# 02ux.net
KiCad netlist of a schematic drawn in Altium Designer
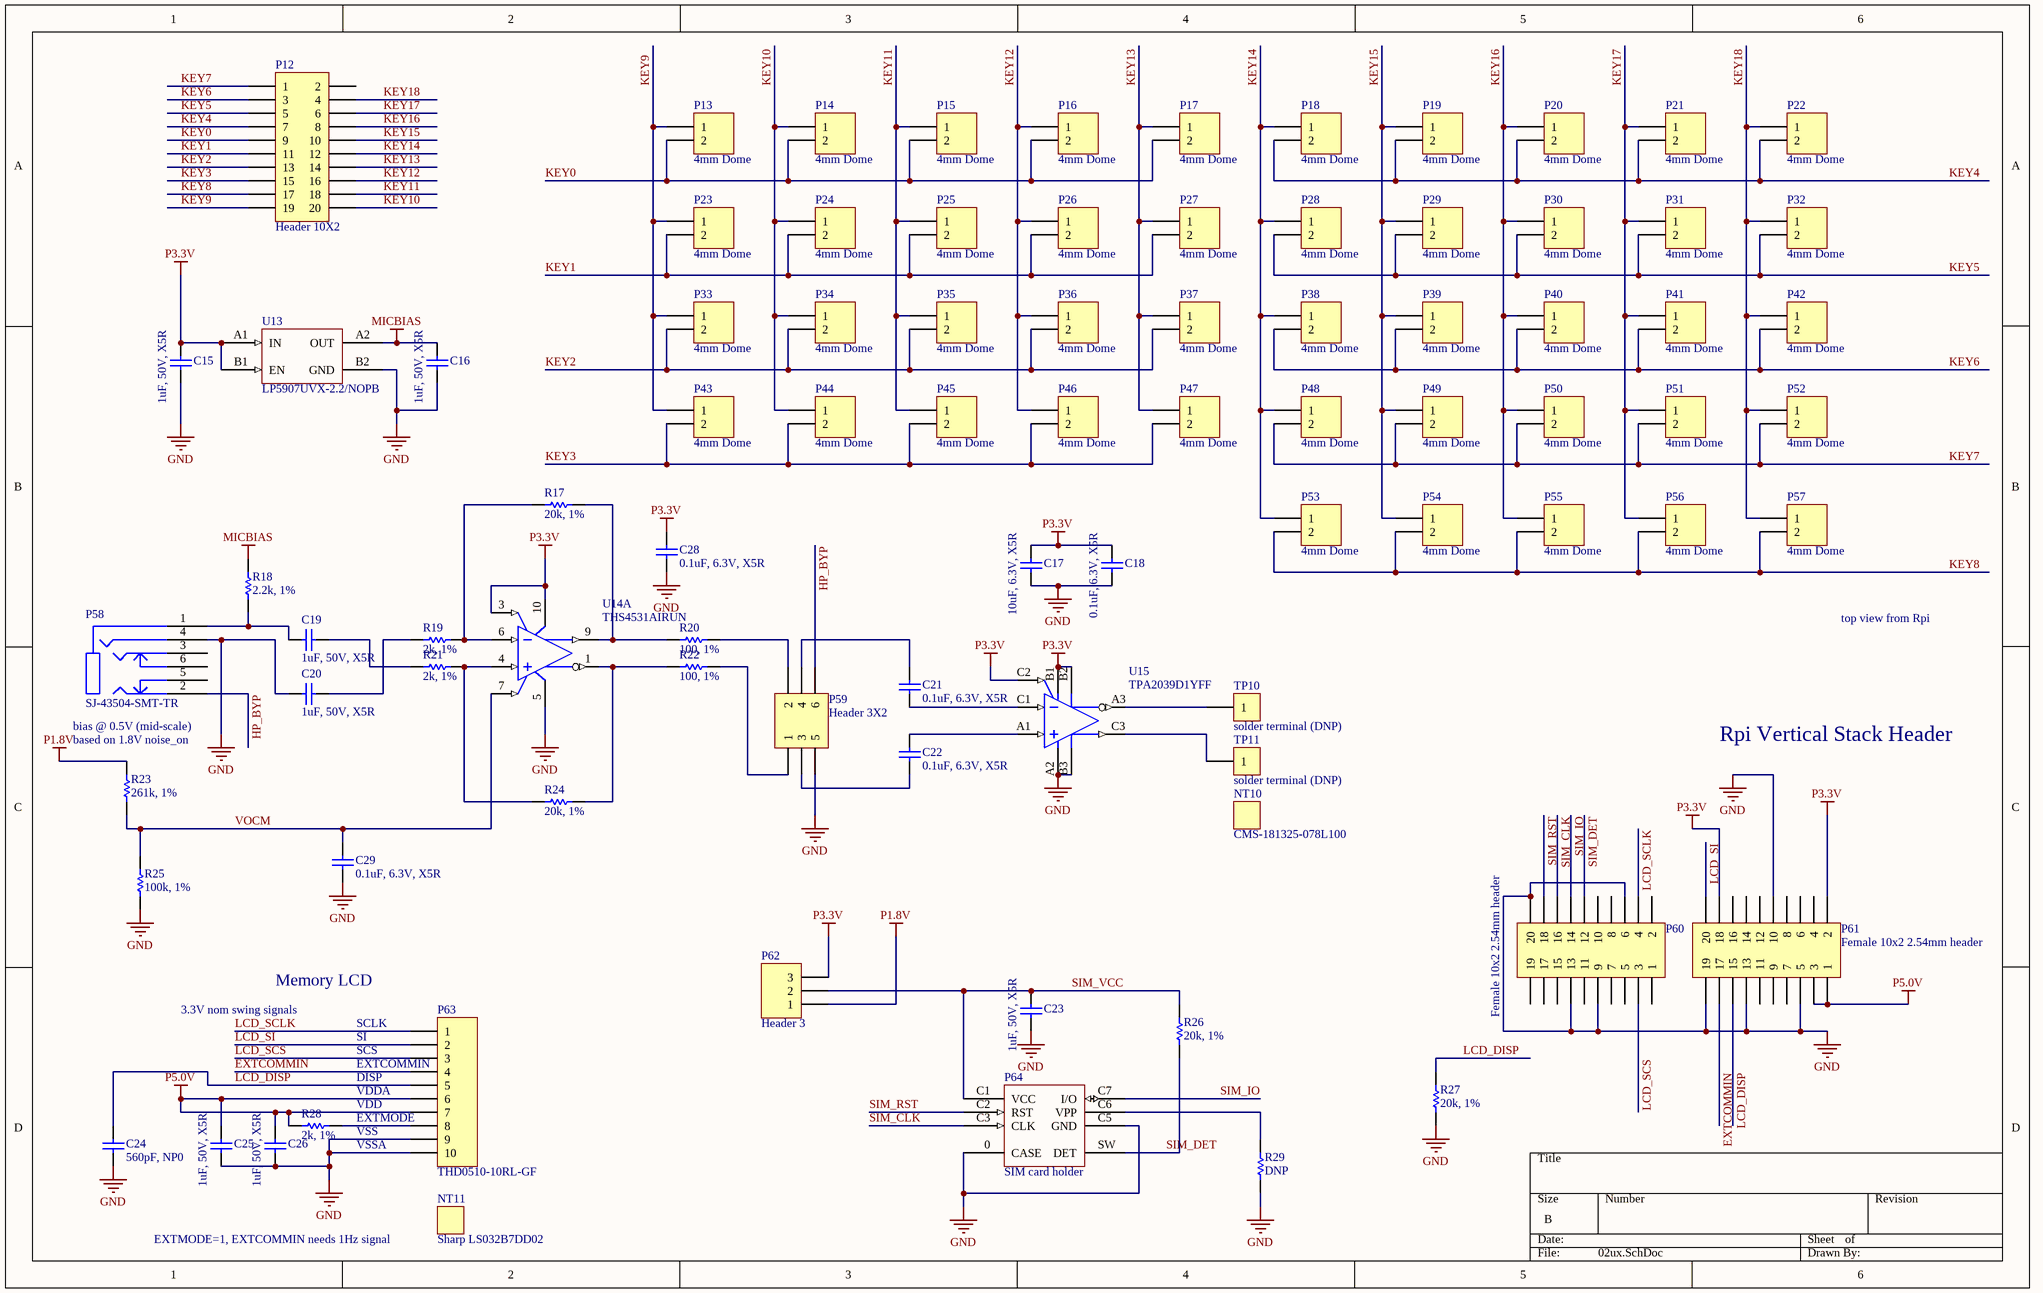
[diagram p0: 02ux.SchDoc]

(export (version "E")
  (design (tool "Eeschema 10.0.6"))
  (components
    (comp (ref "C15")
      (value "1uF, 50V, X5R")
      (footprint "B_CAP0603")
      (description "Capacitor (Semiconductor SIM Model)")
      (fields (field (name "MPN") "CL10A105KB8NNNC"))
      (libsource (lib "Miscellaneous Devices") (part "Cap Semi"))
    )
    (comp (ref "C16")
      (value "1uF, 50V, X5R")
      (footprint "B_CAP0603")
      (description "Capacitor (Semiconductor SIM Model)")
      (fields (field (name "MPN") "CL10A105KB8NNNC"))
      (libsource (lib "Miscellaneous Devices") (part "Cap Semi"))
    )
    (comp (ref "C17")
      (value "10uF, 6.3V, X5R")
      (footprint "B_CAP0603")
      (description "Capacitor (Semiconductor SIM Model)")
      (fields (field (name "MPN") "CL10A106MQ8NNNC"))
      (libsource (lib "Miscellaneous Devices") (part "Cap Semi"))
    )
    (comp (ref "C18")
      (value "0.1uF, 6.3V, X5R")
      (footprint "B_CAP0603")
      (description "Capacitor (Semiconductor SIM Model)")
      (fields (field (name "MPN") "ANY"))
      (libsource (lib "Miscellaneous Devices") (part "Cap Semi"))
    )
    (comp (ref "C19")
      (value "1uF, 50V, X5R")
      (footprint "B_CAP0603")
      (description "Capacitor (Semiconductor SIM Model)")
      (fields (field (name "MPN") "CL10A105KB8NNNC"))
      (libsource (lib "Miscellaneous Devices") (part "Cap Semi"))
    )
    (comp (ref "C20")
      (value "1uF, 50V, X5R")
      (footprint "B_CAP0603")
      (description "Capacitor (Semiconductor SIM Model)")
      (fields (field (name "MPN") "CL10A105KB8NNNC"))
      (libsource (lib "Miscellaneous Devices") (part "Cap Semi"))
    )
    (comp (ref "C21")
      (value "0.1uF, 6.3V, X5R")
      (footprint "B_CAP0603")
      (description "Capacitor (Semiconductor SIM Model)")
      (fields (field (name "MPN") "ANY"))
      (libsource (lib "Miscellaneous Devices") (part "Cap Semi"))
    )
    (comp (ref "C22")
      (value "0.1uF, 6.3V, X5R")
      (footprint "B_CAP0603")
      (description "Capacitor (Semiconductor SIM Model)")
      (fields (field (name "MPN") "ANY"))
      (libsource (lib "Miscellaneous Devices") (part "Cap Semi"))
    )
    (comp (ref "C23")
      (value "1uF, 50V, X5R")
      (footprint "B_CAP0603")
      (description "Capacitor (Semiconductor SIM Model)")
      (fields (field (name "MPN") "CL10A105KB8NNNC"))
      (libsource (lib "Miscellaneous Devices") (part "Cap Semi"))
    )
    (comp (ref "C24")
      (value "560pF, NP0")
      (footprint "B_CAP0402")
      (description "Capacitor (Semiconductor SIM Model)")
      (fields (field (name "MPN") "GRM0335C1E561JA01D"))
      (libsource (lib "Miscellaneous Devices") (part "Cap Semi"))
    )
    (comp (ref "C25")
      (value "1uF, 50V, X5R")
      (footprint "B_CAP0603")
      (description "Capacitor (Semiconductor SIM Model)")
      (fields (field (name "MPN") "CL10A105KB8NNNC"))
      (libsource (lib "Miscellaneous Devices") (part "Cap Semi"))
    )
    (comp (ref "C26")
      (value "1uF, 50V, X5R")
      (footprint "B_CAP0603")
      (description "Capacitor (Semiconductor SIM Model)")
      (fields (field (name "MPN") "CL10A105KB8NNNC"))
      (libsource (lib "Miscellaneous Devices") (part "Cap Semi"))
    )
    (comp (ref "C28")
      (value "0.1uF, 6.3V, X5R")
      (footprint "B_CAP0603")
      (description "Capacitor (Semiconductor SIM Model)")
      (fields (field (name "MPN") "ANY"))
      (libsource (lib "Miscellaneous Devices") (part "Cap Semi"))
    )
    (comp (ref "C29")
      (value "0.1uF, 6.3V, X5R")
      (footprint "B_CAP0603")
      (description "Capacitor (Semiconductor SIM Model)")
      (fields (field (name "MPN") "ANY"))
      (libsource (lib "Miscellaneous Devices") (part "Cap Semi"))
    )
    (comp (ref "NT10")
      (value "CMS-181325-078L100")
      (description "Placeholder for non-board BOM items")
      (libsource (lib "commonsch") (part "NOTE"))
    )
    (comp (ref "NT11")
      (value "Sharp LS032B7DD02")
      (description "Placeholder for non-board BOM items")
      (fields (field (name "MPN") "LS032B7DD02"))
      (libsource (lib "commonsch") (part "NOTE"))
    )
    (comp (ref "P12")
      (value "Header 10X2")
      (footprint "HDR2X10")
      (description "Header, 10-Pin, Dual row")
      (fields (field (name "PUBLISHER") "Altium Limited"))
      (libsource (lib "Miscellaneous Connectors") (part "Header 10X2"))
    )
    (comp (ref "P13")
      (value "4mm Dome")
      (footprint "4MM_DOME_SW")
      (description "Header, 2-Pin")
      (fields (field (name "PUBLISHER") "Altium Limited"))
      (libsource (lib "Miscellaneous Connectors") (part "Header 2"))
    )
    (comp (ref "P14")
      (value "4mm Dome")
      (footprint "4MM_DOME_SW")
      (description "Header, 2-Pin")
      (fields (field (name "PUBLISHER") "Altium Limited"))
      (libsource (lib "Miscellaneous Connectors") (part "Header 2"))
    )
    (comp (ref "P15")
      (value "4mm Dome")
      (footprint "4MM_DOME_SW")
      (description "Header, 2-Pin")
      (fields (field (name "PUBLISHER") "Altium Limited"))
      (libsource (lib "Miscellaneous Connectors") (part "Header 2"))
    )
    (comp (ref "P16")
      (value "4mm Dome")
      (footprint "4MM_DOME_SW")
      (description "Header, 2-Pin")
      (fields (field (name "PUBLISHER") "Altium Limited"))
      (libsource (lib "Miscellaneous Connectors") (part "Header 2"))
    )
    (comp (ref "P17")
      (value "4mm Dome")
      (footprint "4MM_DOME_SW")
      (description "Header, 2-Pin")
      (fields (field (name "PUBLISHER") "Altium Limited"))
      (libsource (lib "Miscellaneous Connectors") (part "Header 2"))
    )
    (comp (ref "P18")
      (value "4mm Dome")
      (footprint "4MM_DOME_SW")
      (description "Header, 2-Pin")
      (fields (field (name "PUBLISHER") "Altium Limited"))
      (libsource (lib "Miscellaneous Connectors") (part "Header 2"))
    )
    (comp (ref "P19")
      (value "4mm Dome")
      (footprint "4MM_DOME_SW")
      (description "Header, 2-Pin")
      (fields (field (name "PUBLISHER") "Altium Limited"))
      (libsource (lib "Miscellaneous Connectors") (part "Header 2"))
    )
    (comp (ref "P20")
      (value "4mm Dome")
      (footprint "4MM_DOME_SW")
      (description "Header, 2-Pin")
      (fields (field (name "PUBLISHER") "Altium Limited"))
      (libsource (lib "Miscellaneous Connectors") (part "Header 2"))
    )
    (comp (ref "P21")
      (value "4mm Dome")
      (footprint "4MM_DOME_SW")
      (description "Header, 2-Pin")
      (fields (field (name "PUBLISHER") "Altium Limited"))
      (libsource (lib "Miscellaneous Connectors") (part "Header 2"))
    )
    (comp (ref "P22")
      (value "4mm Dome")
      (footprint "4MM_DOME_SW")
      (description "Header, 2-Pin")
      (fields (field (name "PUBLISHER") "Altium Limited"))
      (libsource (lib "Miscellaneous Connectors") (part "Header 2"))
    )
    (comp (ref "P23")
      (value "4mm Dome")
      (footprint "4MM_DOME_SW")
      (description "Header, 2-Pin")
      (fields (field (name "PUBLISHER") "Altium Limited"))
      (libsource (lib "Miscellaneous Connectors") (part "Header 2"))
    )
    (comp (ref "P24")
      (value "4mm Dome")
      (footprint "4MM_DOME_SW")
      (description "Header, 2-Pin")
      (fields (field (name "PUBLISHER") "Altium Limited"))
      (libsource (lib "Miscellaneous Connectors") (part "Header 2"))
    )
    (comp (ref "P25")
      (value "4mm Dome")
      (footprint "4MM_DOME_SW")
      (description "Header, 2-Pin")
      (fields (field (name "PUBLISHER") "Altium Limited"))
      (libsource (lib "Miscellaneous Connectors") (part "Header 2"))
    )
    (comp (ref "P26")
      (value "4mm Dome")
      (footprint "4MM_DOME_SW")
      (description "Header, 2-Pin")
      (fields (field (name "PUBLISHER") "Altium Limited"))
      (libsource (lib "Miscellaneous Connectors") (part "Header 2"))
    )
    (comp (ref "P27")
      (value "4mm Dome")
      (footprint "4MM_DOME_SW")
      (description "Header, 2-Pin")
      (fields (field (name "PUBLISHER") "Altium Limited"))
      (libsource (lib "Miscellaneous Connectors") (part "Header 2"))
    )
    (comp (ref "P28")
      (value "4mm Dome")
      (footprint "4MM_DOME_SW")
      (description "Header, 2-Pin")
      (fields (field (name "PUBLISHER") "Altium Limited"))
      (libsource (lib "Miscellaneous Connectors") (part "Header 2"))
    )
    (comp (ref "P29")
      (value "4mm Dome")
      (footprint "4MM_DOME_SW")
      (description "Header, 2-Pin")
      (fields (field (name "PUBLISHER") "Altium Limited"))
      (libsource (lib "Miscellaneous Connectors") (part "Header 2"))
    )
    (comp (ref "P30")
      (value "4mm Dome")
      (footprint "4MM_DOME_SW")
      (description "Header, 2-Pin")
      (fields (field (name "PUBLISHER") "Altium Limited"))
      (libsource (lib "Miscellaneous Connectors") (part "Header 2"))
    )
    (comp (ref "P31")
      (value "4mm Dome")
      (footprint "4MM_DOME_SW")
      (description "Header, 2-Pin")
      (fields (field (name "PUBLISHER") "Altium Limited"))
      (libsource (lib "Miscellaneous Connectors") (part "Header 2"))
    )
    (comp (ref "P32")
      (value "4mm Dome")
      (footprint "4MM_DOME_SW")
      (description "Header, 2-Pin")
      (fields (field (name "PUBLISHER") "Altium Limited"))
      (libsource (lib "Miscellaneous Connectors") (part "Header 2"))
    )
    (comp (ref "P33")
      (value "4mm Dome")
      (footprint "4MM_DOME_SW")
      (description "Header, 2-Pin")
      (fields (field (name "PUBLISHER") "Altium Limited"))
      (libsource (lib "Miscellaneous Connectors") (part "Header 2"))
    )
    (comp (ref "P34")
      (value "4mm Dome")
      (footprint "4MM_DOME_SW")
      (description "Header, 2-Pin")
      (fields (field (name "PUBLISHER") "Altium Limited"))
      (libsource (lib "Miscellaneous Connectors") (part "Header 2"))
    )
    (comp (ref "P35")
      (value "4mm Dome")
      (footprint "4MM_DOME_SW")
      (description "Header, 2-Pin")
      (fields (field (name "PUBLISHER") "Altium Limited"))
      (libsource (lib "Miscellaneous Connectors") (part "Header 2"))
    )
    (comp (ref "P36")
      (value "4mm Dome")
      (footprint "4MM_DOME_SW")
      (description "Header, 2-Pin")
      (fields (field (name "PUBLISHER") "Altium Limited"))
      (libsource (lib "Miscellaneous Connectors") (part "Header 2"))
    )
    (comp (ref "P37")
      (value "4mm Dome")
      (footprint "4MM_DOME_SW")
      (description "Header, 2-Pin")
      (fields (field (name "PUBLISHER") "Altium Limited"))
      (libsource (lib "Miscellaneous Connectors") (part "Header 2"))
    )
    (comp (ref "P38")
      (value "4mm Dome")
      (footprint "4MM_DOME_SW")
      (description "Header, 2-Pin")
      (fields (field (name "PUBLISHER") "Altium Limited"))
      (libsource (lib "Miscellaneous Connectors") (part "Header 2"))
    )
    (comp (ref "P39")
      (value "4mm Dome")
      (footprint "4MM_DOME_SW")
      (description "Header, 2-Pin")
      (fields (field (name "PUBLISHER") "Altium Limited"))
      (libsource (lib "Miscellaneous Connectors") (part "Header 2"))
    )
    (comp (ref "P40")
      (value "4mm Dome")
      (footprint "4MM_DOME_SW")
      (description "Header, 2-Pin")
      (fields (field (name "PUBLISHER") "Altium Limited"))
      (libsource (lib "Miscellaneous Connectors") (part "Header 2"))
    )
    (comp (ref "P41")
      (value "4mm Dome")
      (footprint "4MM_DOME_SW")
      (description "Header, 2-Pin")
      (fields (field (name "PUBLISHER") "Altium Limited"))
      (libsource (lib "Miscellaneous Connectors") (part "Header 2"))
    )
    (comp (ref "P42")
      (value "4mm Dome")
      (footprint "4MM_DOME_SW")
      (description "Header, 2-Pin")
      (fields (field (name "PUBLISHER") "Altium Limited"))
      (libsource (lib "Miscellaneous Connectors") (part "Header 2"))
    )
    (comp (ref "P43")
      (value "4mm Dome")
      (footprint "4MM_DOME_SW")
      (description "Header, 2-Pin")
      (fields (field (name "PUBLISHER") "Altium Limited"))
      (libsource (lib "Miscellaneous Connectors") (part "Header 2"))
    )
    (comp (ref "P44")
      (value "4mm Dome")
      (footprint "4MM_DOME_SW")
      (description "Header, 2-Pin")
      (fields (field (name "PUBLISHER") "Altium Limited"))
      (libsource (lib "Miscellaneous Connectors") (part "Header 2"))
    )
    (comp (ref "P45")
      (value "4mm Dome")
      (footprint "4MM_DOME_SW")
      (description "Header, 2-Pin")
      (fields (field (name "PUBLISHER") "Altium Limited"))
      (libsource (lib "Miscellaneous Connectors") (part "Header 2"))
    )
    (comp (ref "P46")
      (value "4mm Dome")
      (footprint "4MM_DOME_SW")
      (description "Header, 2-Pin")
      (fields (field (name "PUBLISHER") "Altium Limited"))
      (libsource (lib "Miscellaneous Connectors") (part "Header 2"))
    )
    (comp (ref "P47")
      (value "4mm Dome")
      (footprint "4MM_DOME_SW")
      (description "Header, 2-Pin")
      (fields (field (name "PUBLISHER") "Altium Limited"))
      (libsource (lib "Miscellaneous Connectors") (part "Header 2"))
    )
    (comp (ref "P48")
      (value "4mm Dome")
      (footprint "4MM_DOME_SW")
      (description "Header, 2-Pin")
      (fields (field (name "PUBLISHER") "Altium Limited"))
      (libsource (lib "Miscellaneous Connectors") (part "Header 2"))
    )
    (comp (ref "P49")
      (value "4mm Dome")
      (footprint "4MM_DOME_SW")
      (description "Header, 2-Pin")
      (fields (field (name "PUBLISHER") "Altium Limited"))
      (libsource (lib "Miscellaneous Connectors") (part "Header 2"))
    )
    (comp (ref "P50")
      (value "4mm Dome")
      (footprint "4MM_DOME_SW")
      (description "Header, 2-Pin")
      (fields (field (name "PUBLISHER") "Altium Limited"))
      (libsource (lib "Miscellaneous Connectors") (part "Header 2"))
    )
    (comp (ref "P51")
      (value "4mm Dome")
      (footprint "4MM_DOME_SW")
      (description "Header, 2-Pin")
      (fields (field (name "PUBLISHER") "Altium Limited"))
      (libsource (lib "Miscellaneous Connectors") (part "Header 2"))
    )
    (comp (ref "P52")
      (value "4mm Dome")
      (footprint "4MM_DOME_SW")
      (description "Header, 2-Pin")
      (fields (field (name "PUBLISHER") "Altium Limited"))
      (libsource (lib "Miscellaneous Connectors") (part "Header 2"))
    )
    (comp (ref "P53")
      (value "4mm Dome")
      (footprint "4MM_DOME_SW")
      (description "Header, 2-Pin")
      (fields (field (name "PUBLISHER") "Altium Limited"))
      (libsource (lib "Miscellaneous Connectors") (part "Header 2"))
    )
    (comp (ref "P54")
      (value "4mm Dome")
      (footprint "4MM_DOME_SW")
      (description "Header, 2-Pin")
      (fields (field (name "PUBLISHER") "Altium Limited"))
      (libsource (lib "Miscellaneous Connectors") (part "Header 2"))
    )
    (comp (ref "P55")
      (value "4mm Dome")
      (footprint "4MM_DOME_SW")
      (description "Header, 2-Pin")
      (fields (field (name "PUBLISHER") "Altium Limited"))
      (libsource (lib "Miscellaneous Connectors") (part "Header 2"))
    )
    (comp (ref "P56")
      (value "4mm Dome")
      (footprint "4MM_DOME_SW")
      (description "Header, 2-Pin")
      (fields (field (name "PUBLISHER") "Altium Limited"))
      (libsource (lib "Miscellaneous Connectors") (part "Header 2"))
    )
    (comp (ref "P57")
      (value "4mm Dome")
      (footprint "4MM_DOME_SW")
      (description "Header, 2-Pin")
      (fields (field (name "PUBLISHER") "Altium Limited"))
      (libsource (lib "Miscellaneous Connectors") (part "Header 2"))
    )
    (comp (ref "P58")
      (value "SJ-43504-SMT-TR")
      (footprint "CUI_SJ_43504_SMT_TR_PULLBACK")
      (description "Mid mount audio jack")
      (libsource (lib "commonsch-new") (part "CUI_3.5MM_STEREO_MIC"))
    )
    (comp (ref "P59")
      (value "Header 3X2")
      (footprint "HDR2X3")
      (description "Header, 3-Pin, Dual row")
      (fields (field (name "PUBLISHER") "Altium Limited"))
      (libsource (lib "Miscellaneous Connectors") (part "Header 3X2"))
    )
    (comp (ref "P60")
      (value "Female 10x2 2.54mm header")
      (footprint "HDR2X10")
      (description "Header, 10-Pin, Dual row")
      (fields (field (name "MPN") "F201-SGP-D048-20-P4") (field (name "PUBLISHER") "Altium Limited"))
      (libsource (lib "Miscellaneous Connectors") (part "Header 10X2"))
    )
    (comp (ref "P61")
      (value "Female 10x2 2.54mm header")
      (footprint "HDR2X10")
      (description "Header, 10-Pin, Dual row")
      (fields (field (name "MPN") "F201-SGP-D048-20-P4") (field (name "PUBLISHER") "Altium Limited"))
      (libsource (lib "Miscellaneous Connectors") (part "Header 10X2"))
    )
    (comp (ref "P62")
      (value "Header 3")
      (footprint "HDR1X3")
      (description "Header, 3-Pin")
      (fields (field (name "PUBLISHER") "Altium Limited"))
      (libsource (lib "Miscellaneous Connectors") (part "Header 3"))
    )
    (comp (ref "P63")
      (value "THD0510-10RL-GF")
      (footprint "KAWEEI_THD0510_10RL_GF")
      (description "Header, 10-Pin")
      (fields (field (name "PUBLISHER") "Altium Limited"))
      (libsource (lib "Miscellaneous Connectors") (part "Header 10"))
    )
    (comp (ref "P64")
      (value "SIM card holder")
      (footprint "MOLEX_504520_0691")
      (fields (field (name "MPN") "504520-0691"))
      (libsource (lib "commonsch-new") (part "SIM_SLOT"))
    )
    (comp (ref "R17")
      (value "20k, 1%")
      (footprint "B_RES0402")
      (description "Resistor")
      (fields (field (name "MPN") "ANY"))
      (libsource (lib "Miscellaneous Devices") (part "Res1"))
    )
    (comp (ref "R18")
      (value "2.2k, 1%")
      (footprint "B_RES0402")
      (description "Resistor")
      (fields (field (name "MPN") "ANY"))
      (libsource (lib "Miscellaneous Devices") (part "Res1"))
    )
    (comp (ref "R19")
      (value "2k, 1%")
      (footprint "B_RES0402")
      (description "Resistor")
      (fields (field (name "MPN") "ANY"))
      (libsource (lib "Miscellaneous Devices") (part "Res1"))
    )
    (comp (ref "R20")
      (value "100, 1%")
      (footprint "B_RES0402")
      (description "Resistor")
      (fields (field (name "MPN") "ANY"))
      (libsource (lib "Miscellaneous Devices") (part "Res1"))
    )
    (comp (ref "R21")
      (value "2k, 1%")
      (footprint "B_RES0402")
      (description "Resistor")
      (fields (field (name "MPN") "ANY"))
      (libsource (lib "Miscellaneous Devices") (part "Res1"))
    )
    (comp (ref "R22")
      (value "100, 1%")
      (footprint "B_RES0402")
      (description "Resistor")
      (fields (field (name "MPN") "ANY"))
      (libsource (lib "Miscellaneous Devices") (part "Res1"))
    )
    (comp (ref "R23")
      (value "261k, 1%")
      (footprint "B_RES0402")
      (description "Resistor")
      (fields (field (name "MPN") "ANY"))
      (libsource (lib "Miscellaneous Devices") (part "Res1"))
    )
    (comp (ref "R24")
      (value "20k, 1%")
      (footprint "B_RES0402")
      (description "Resistor")
      (fields (field (name "MPN") "ANY"))
      (libsource (lib "Miscellaneous Devices") (part "Res1"))
    )
    (comp (ref "R25")
      (value "100k, 1%")
      (footprint "B_RES0402")
      (description "Resistor")
      (fields (field (name "MPN") "ANY"))
      (libsource (lib "Miscellaneous Devices") (part "Res1"))
    )
    (comp (ref "R26")
      (value "20k, 1%")
      (footprint "B_RES0402")
      (description "Resistor")
      (fields (field (name "MPN") "ANY"))
      (libsource (lib "Miscellaneous Devices") (part "Res1"))
    )
    (comp (ref "R27")
      (value "20k, 1%")
      (footprint "B_RES0402")
      (description "Resistor")
      (fields (field (name "MPN") "ANY"))
      (libsource (lib "Miscellaneous Devices") (part "Res1"))
    )
    (comp (ref "R28")
      (value "2k, 1%")
      (footprint "B_RES0402")
      (description "Resistor")
      (fields (field (name "MPN") "ANY"))
      (libsource (lib "Miscellaneous Devices") (part "Res1"))
    )
    (comp (ref "R29")
      (value "DNP")
      (footprint "B_RES0402")
      (description "Resistor")
      (fields (field (name "MPN") "ANY"))
      (libsource (lib "Miscellaneous Devices") (part "Res1"))
    )
    (comp (ref "TP10")
      (value "solder terminal (DNP)")
      (footprint "55-MIL-HOLE")
      (description "Connector")
      (libsource (lib "*") (part "CON1"))
    )
    (comp (ref "TP11")
      (value "solder terminal (DNP)")
      (footprint "55-MIL-HOLE")
      (description "Connector")
      (libsource (lib "*") (part "CON1"))
    )
    (comp (ref "U13")
      (value "LP5907UVX-2.2/NOPB")
      (footprint "TI_YKE004")
      (description "Ultra low-noise 250mA LDO for RF and analog in DSBGA")
      (libsource (lib "commonsch-new") (part "LP5907UVX"))
    )
    (comp (ref "U14")
      (value "THS4531AIRUN")
      (footprint "RUN0010A")
      (description "Ultra Low-Power, RRIO, Fully Differential Amplifier")
      (fields (field (name "MPN") "THS4531AIRUN(T/R)"))
      (libsource (lib "TI-THS4531X-RUN10") (part "TI-THS4531X-RUN10"))
    )
    (comp (ref "U15")
      (value "TPA2039D1YFF")
      (footprint "YFF0009AAAC")
      (description "3.2W Mono Class-D Audio Power Amplifier With 12-dB Gain and Auto Short-Circuit Recovery")
      (fields (field (name "MPN") "TPA2039D1YFF(T/R)"))
      (libsource (lib "TI-TPA20XXD1YFF9") (part "TI-TPA20XXD1YFF9"))
    )
  )
  (nets
    (net (code "1") (name "/EXTCOMMIN") (class "Default")
      (node (ref "P61") (pin "17") (pinfunction "17_17") (pintype "passive"))
      (node (ref "P63") (pin "4") (pinfunction "4_4") (pintype "passive"))
    )
    (net (code "2") (name "/HP_BYP") (class "Default")
      (node (ref "P58") (pin "2") (pinfunction "TIP_2") (pintype "passive"))
      (node (ref "P59") (pin "6") (pinfunction "6_6") (pintype "passive"))
    )
    (net (code "3") (name "/KEY0") (class "Default")
      (node (ref "P12") (pin "9") (pinfunction "9_9") (pintype "passive"))
      (node (ref "P13") (pin "2") (pinfunction "2_2") (pintype "passive"))
      (node (ref "P14") (pin "2") (pinfunction "2_2") (pintype "passive"))
      (node (ref "P15") (pin "2") (pinfunction "2_2") (pintype "passive"))
      (node (ref "P16") (pin "2") (pinfunction "2_2") (pintype "passive"))
      (node (ref "P17") (pin "2") (pinfunction "2_2") (pintype "passive"))
    )
    (net (code "4") (name "/KEY1") (class "Default")
      (node (ref "P12") (pin "11") (pinfunction "11_11") (pintype "passive"))
      (node (ref "P23") (pin "2") (pinfunction "2_2") (pintype "passive"))
      (node (ref "P24") (pin "2") (pinfunction "2_2") (pintype "passive"))
      (node (ref "P25") (pin "2") (pinfunction "2_2") (pintype "passive"))
      (node (ref "P26") (pin "2") (pinfunction "2_2") (pintype "passive"))
      (node (ref "P27") (pin "2") (pinfunction "2_2") (pintype "passive"))
    )
    (net (code "5") (name "/KEY2") (class "Default")
      (node (ref "P12") (pin "13") (pinfunction "13_13") (pintype "passive"))
      (node (ref "P33") (pin "2") (pinfunction "2_2") (pintype "passive"))
      (node (ref "P34") (pin "2") (pinfunction "2_2") (pintype "passive"))
      (node (ref "P35") (pin "2") (pinfunction "2_2") (pintype "passive"))
      (node (ref "P36") (pin "2") (pinfunction "2_2") (pintype "passive"))
      (node (ref "P37") (pin "2") (pinfunction "2_2") (pintype "passive"))
    )
    (net (code "6") (name "/KEY3") (class "Default")
      (node (ref "P12") (pin "15") (pinfunction "15_15") (pintype "passive"))
      (node (ref "P43") (pin "2") (pinfunction "2_2") (pintype "passive"))
      (node (ref "P44") (pin "2") (pinfunction "2_2") (pintype "passive"))
      (node (ref "P45") (pin "2") (pinfunction "2_2") (pintype "passive"))
      (node (ref "P46") (pin "2") (pinfunction "2_2") (pintype "passive"))
      (node (ref "P47") (pin "2") (pinfunction "2_2") (pintype "passive"))
    )
    (net (code "7") (name "/KEY4") (class "Default")
      (node (ref "P12") (pin "7") (pinfunction "7_7") (pintype "passive"))
      (node (ref "P18") (pin "2") (pinfunction "2_2") (pintype "passive"))
      (node (ref "P19") (pin "2") (pinfunction "2_2") (pintype "passive"))
      (node (ref "P20") (pin "2") (pinfunction "2_2") (pintype "passive"))
      (node (ref "P21") (pin "2") (pinfunction "2_2") (pintype "passive"))
      (node (ref "P22") (pin "2") (pinfunction "2_2") (pintype "passive"))
    )
    (net (code "8") (name "/KEY5") (class "Default")
      (node (ref "P12") (pin "5") (pinfunction "5_5") (pintype "passive"))
      (node (ref "P28") (pin "2") (pinfunction "2_2") (pintype "passive"))
      (node (ref "P29") (pin "2") (pinfunction "2_2") (pintype "passive"))
      (node (ref "P30") (pin "2") (pinfunction "2_2") (pintype "passive"))
      (node (ref "P31") (pin "2") (pinfunction "2_2") (pintype "passive"))
      (node (ref "P32") (pin "2") (pinfunction "2_2") (pintype "passive"))
    )
    (net (code "9") (name "/KEY6") (class "Default")
      (node (ref "P12") (pin "3") (pinfunction "3_3") (pintype "passive"))
      (node (ref "P38") (pin "2") (pinfunction "2_2") (pintype "passive"))
      (node (ref "P39") (pin "2") (pinfunction "2_2") (pintype "passive"))
      (node (ref "P40") (pin "2") (pinfunction "2_2") (pintype "passive"))
      (node (ref "P41") (pin "2") (pinfunction "2_2") (pintype "passive"))
      (node (ref "P42") (pin "2") (pinfunction "2_2") (pintype "passive"))
    )
    (net (code "10") (name "/KEY7") (class "Default")
      (node (ref "P12") (pin "1") (pinfunction "1_1") (pintype "passive"))
      (node (ref "P48") (pin "2") (pinfunction "2_2") (pintype "passive"))
      (node (ref "P49") (pin "2") (pinfunction "2_2") (pintype "passive"))
      (node (ref "P50") (pin "2") (pinfunction "2_2") (pintype "passive"))
      (node (ref "P51") (pin "2") (pinfunction "2_2") (pintype "passive"))
      (node (ref "P52") (pin "2") (pinfunction "2_2") (pintype "passive"))
    )
    (net (code "11") (name "/KEY8") (class "Default")
      (node (ref "P12") (pin "17") (pinfunction "17_17") (pintype "passive"))
      (node (ref "P53") (pin "2") (pinfunction "2_2") (pintype "passive"))
      (node (ref "P54") (pin "2") (pinfunction "2_2") (pintype "passive"))
      (node (ref "P55") (pin "2") (pinfunction "2_2") (pintype "passive"))
      (node (ref "P56") (pin "2") (pinfunction "2_2") (pintype "passive"))
      (node (ref "P57") (pin "2") (pinfunction "2_2") (pintype "passive"))
    )
    (net (code "12") (name "/KEY9") (class "Default")
      (node (ref "P12") (pin "19") (pinfunction "19_19") (pintype "passive"))
      (node (ref "P13") (pin "1") (pinfunction "1_1") (pintype "passive"))
      (node (ref "P23") (pin "1") (pinfunction "1_1") (pintype "passive"))
      (node (ref "P33") (pin "1") (pinfunction "1_1") (pintype "passive"))
      (node (ref "P43") (pin "1") (pinfunction "1_1") (pintype "passive"))
    )
    (net (code "13") (name "/KEY10") (class "Default")
      (node (ref "P12") (pin "20") (pinfunction "20_20") (pintype "passive"))
      (node (ref "P14") (pin "1") (pinfunction "1_1") (pintype "passive"))
      (node (ref "P24") (pin "1") (pinfunction "1_1") (pintype "passive"))
      (node (ref "P34") (pin "1") (pinfunction "1_1") (pintype "passive"))
      (node (ref "P44") (pin "1") (pinfunction "1_1") (pintype "passive"))
    )
    (net (code "14") (name "/KEY11") (class "Default")
      (node (ref "P12") (pin "18") (pinfunction "18_18") (pintype "passive"))
      (node (ref "P15") (pin "1") (pinfunction "1_1") (pintype "passive"))
      (node (ref "P25") (pin "1") (pinfunction "1_1") (pintype "passive"))
      (node (ref "P35") (pin "1") (pinfunction "1_1") (pintype "passive"))
      (node (ref "P45") (pin "1") (pinfunction "1_1") (pintype "passive"))
    )
    (net (code "15") (name "/KEY12") (class "Default")
      (node (ref "P12") (pin "16") (pinfunction "16_16") (pintype "passive"))
      (node (ref "P16") (pin "1") (pinfunction "1_1") (pintype "passive"))
      (node (ref "P26") (pin "1") (pinfunction "1_1") (pintype "passive"))
      (node (ref "P36") (pin "1") (pinfunction "1_1") (pintype "passive"))
      (node (ref "P46") (pin "1") (pinfunction "1_1") (pintype "passive"))
    )
    (net (code "16") (name "/KEY13") (class "Default")
      (node (ref "P12") (pin "14") (pinfunction "14_14") (pintype "passive"))
      (node (ref "P17") (pin "1") (pinfunction "1_1") (pintype "passive"))
      (node (ref "P27") (pin "1") (pinfunction "1_1") (pintype "passive"))
      (node (ref "P37") (pin "1") (pinfunction "1_1") (pintype "passive"))
      (node (ref "P47") (pin "1") (pinfunction "1_1") (pintype "passive"))
    )
    (net (code "17") (name "/KEY14") (class "Default")
      (node (ref "P12") (pin "12") (pinfunction "12_12") (pintype "passive"))
      (node (ref "P18") (pin "1") (pinfunction "1_1") (pintype "passive"))
      (node (ref "P28") (pin "1") (pinfunction "1_1") (pintype "passive"))
      (node (ref "P38") (pin "1") (pinfunction "1_1") (pintype "passive"))
      (node (ref "P48") (pin "1") (pinfunction "1_1") (pintype "passive"))
      (node (ref "P53") (pin "1") (pinfunction "1_1") (pintype "passive"))
    )
    (net (code "18") (name "/KEY15") (class "Default")
      (node (ref "P12") (pin "10") (pinfunction "10_10") (pintype "passive"))
      (node (ref "P19") (pin "1") (pinfunction "1_1") (pintype "passive"))
      (node (ref "P29") (pin "1") (pinfunction "1_1") (pintype "passive"))
      (node (ref "P39") (pin "1") (pinfunction "1_1") (pintype "passive"))
      (node (ref "P49") (pin "1") (pinfunction "1_1") (pintype "passive"))
      (node (ref "P54") (pin "1") (pinfunction "1_1") (pintype "passive"))
    )
    (net (code "19") (name "/KEY16") (class "Default")
      (node (ref "P12") (pin "8") (pinfunction "8_8") (pintype "passive"))
      (node (ref "P20") (pin "1") (pinfunction "1_1") (pintype "passive"))
      (node (ref "P30") (pin "1") (pinfunction "1_1") (pintype "passive"))
      (node (ref "P40") (pin "1") (pinfunction "1_1") (pintype "passive"))
      (node (ref "P50") (pin "1") (pinfunction "1_1") (pintype "passive"))
      (node (ref "P55") (pin "1") (pinfunction "1_1") (pintype "passive"))
    )
    (net (code "20") (name "/KEY17") (class "Default")
      (node (ref "P12") (pin "6") (pinfunction "6_6") (pintype "passive"))
      (node (ref "P21") (pin "1") (pinfunction "1_1") (pintype "passive"))
      (node (ref "P31") (pin "1") (pinfunction "1_1") (pintype "passive"))
      (node (ref "P41") (pin "1") (pinfunction "1_1") (pintype "passive"))
      (node (ref "P51") (pin "1") (pinfunction "1_1") (pintype "passive"))
      (node (ref "P56") (pin "1") (pinfunction "1_1") (pintype "passive"))
    )
    (net (code "21") (name "/KEY18") (class "Default")
      (node (ref "P12") (pin "4") (pinfunction "4_4") (pintype "passive"))
      (node (ref "P22") (pin "1") (pinfunction "1_1") (pintype "passive"))
      (node (ref "P32") (pin "1") (pinfunction "1_1") (pintype "passive"))
      (node (ref "P42") (pin "1") (pinfunction "1_1") (pintype "passive"))
      (node (ref "P52") (pin "1") (pinfunction "1_1") (pintype "passive"))
      (node (ref "P57") (pin "1") (pinfunction "1_1") (pintype "passive"))
    )
    (net (code "22") (name "/LCD_DISP") (class "Default")
      (node (ref "C24") (pin "1") (pinfunction "1_1") (pintype "passive"))
      (node (ref "P61") (pin "15") (pinfunction "15_15") (pintype "passive"))
      (node (ref "P63") (pin "5") (pinfunction "5_5") (pintype "passive"))
      (node (ref "R27") (pin "2") (pinfunction "2_2") (pintype "passive"))
    )
    (net (code "23") (name "/LCD_SCLK") (class "Default")
      (node (ref "P60") (pin "4") (pinfunction "4_4") (pintype "passive"))
      (node (ref "P63") (pin "1") (pinfunction "1_1") (pintype "passive"))
    )
    (net (code "24") (name "/LCD_SCS") (class "Default")
      (node (ref "P60") (pin "3") (pinfunction "3_3") (pintype "passive"))
      (node (ref "P63") (pin "3") (pinfunction "3_3") (pintype "passive"))
    )
    (net (code "25") (name "/LCD_SI") (class "Default")
      (node (ref "P61") (pin "20") (pinfunction "20_20") (pintype "passive"))
      (node (ref "P63") (pin "2") (pinfunction "2_2") (pintype "passive"))
    )
    (net (code "26") (name "/SIM_CLK") (class "Default")
      (node (ref "P60") (pin "16") (pinfunction "16_16") (pintype "passive"))
      (node (ref "P64") (pin "C3") (pinfunction "CLK_C3") (pintype "input"))
    )
    (net (code "27") (name "/SIM_DET") (class "Default")
      (node (ref "P60") (pin "12") (pinfunction "12_12") (pintype "passive"))
      (node (ref "P64") (pin "SW") (pinfunction "DET_SW") (pintype "passive"))
      (node (ref "R26") (pin "1") (pinfunction "1_1") (pintype "passive"))
    )
    (net (code "28") (name "/SIM_IO") (class "Default")
      (node (ref "P60") (pin "14") (pinfunction "14_14") (pintype "passive"))
      (node (ref "P64") (pin "C7") (pinfunction "I/O_C7") (pintype "bidirectional"))
    )
    (net (code "29") (name "/SIM_RST") (class "Default")
      (node (ref "P60") (pin "18") (pinfunction "18_18") (pintype "passive"))
      (node (ref "P64") (pin "C2") (pinfunction "RST_C2") (pintype "input"))
    )
    (net (code "30") (name "/SIM_VCC") (class "Default")
      (node (ref "C23") (pin "1") (pinfunction "1_1") (pintype "passive"))
      (node (ref "P62") (pin "2") (pinfunction "2_2") (pintype "passive"))
      (node (ref "P64") (pin "C1") (pinfunction "VCC_C1") (pintype "power_in"))
      (node (ref "R26") (pin "2") (pinfunction "2_2") (pintype "passive"))
    )
    (net (code "31") (name "/VOCM") (class "Default")
      (node (ref "C29") (pin "2") (pinfunction "2_2") (pintype "passive"))
      (node (ref "R23") (pin "1") (pinfunction "1_1") (pintype "passive"))
      (node (ref "R25") (pin "2") (pinfunction "2_2") (pintype "passive"))
      (node (ref "U14") (pin "7") (pinfunction "VOCM_7") (pintype "input"))
    )
    (net (code "32") (name "GND") (class "Default")
      (node (ref "C15") (pin "2") (pinfunction "2_2") (pintype "passive"))
      (node (ref "C16") (pin "2") (pinfunction "2_2") (pintype "passive"))
      (node (ref "C17") (pin "2") (pinfunction "2_2") (pintype "passive"))
      (node (ref "C18") (pin "2") (pinfunction "2_2") (pintype "passive"))
      (node (ref "C20") (pin "1") (pinfunction "1_1") (pintype "passive"))
      (node (ref "C23") (pin "2") (pinfunction "2_2") (pintype "passive"))
      (node (ref "C24") (pin "2") (pinfunction "2_2") (pintype "passive"))
      (node (ref "C25") (pin "2") (pinfunction "2_2") (pintype "passive"))
      (node (ref "C26") (pin "2") (pinfunction "2_2") (pintype "passive"))
      (node (ref "C28") (pin "1") (pinfunction "1_1") (pintype "passive"))
      (node (ref "C29") (pin "1") (pinfunction "1_1") (pintype "passive"))
      (node (ref "P58") (pin "4") (pinfunction "RING2_4") (pintype "passive"))
      (node (ref "P59") (pin "5") (pinfunction "5_5") (pintype "passive"))
      (node (ref "P60") (pin "13") (pinfunction "13_13") (pintype "passive"))
      (node (ref "P60") (pin "20") (pinfunction "20_20") (pintype "passive"))
      (node (ref "P60") (pin "6") (pinfunction "6_6") (pintype "passive"))
      (node (ref "P60") (pin "9") (pinfunction "9_9") (pintype "passive"))
      (node (ref "P61") (pin "10") (pinfunction "10_10") (pintype "passive"))
      (node (ref "P61") (pin "13") (pinfunction "13_13") (pintype "passive"))
      (node (ref "P61") (pin "19") (pinfunction "19_19") (pintype "passive"))
      (node (ref "P61") (pin "5") (pinfunction "5_5") (pintype "passive"))
      (node (ref "P63") (pin "10") (pinfunction "10_10") (pintype "passive"))
      (node (ref "P63") (pin "9") (pinfunction "9_9") (pintype "passive"))
      (node (ref "P64") (pin "0") (pinfunction "CASE_0") (pintype "passive"))
      (node (ref "P64") (pin "C5") (pinfunction "GND_C5") (pintype "power_in"))
      (node (ref "R25") (pin "1") (pinfunction "1_1") (pintype "passive"))
      (node (ref "R27") (pin "1") (pinfunction "1_1") (pintype "passive"))
      (node (ref "R29") (pin "1") (pinfunction "1_1") (pintype "passive"))
      (node (ref "U13") (pin "B2") (pinfunction "GND_B2") (pintype "power_in"))
      (node (ref "U14") (pin "5") (pinfunction "VS-_5") (pintype "power_in"))
      (node (ref "U15") (pin "A2") (pinfunction "GND_A2") (pintype "power_in"))
      (node (ref "U15") (pin "B3") (pinfunction "PGND_B3") (pintype "power_in"))
    )
    (net (code "33") (name "MICBIAS") (class "Default")
      (node (ref "C16") (pin "1") (pinfunction "1_1") (pintype "passive"))
      (node (ref "R18") (pin "2") (pinfunction "2_2") (pintype "passive"))
      (node (ref "U13") (pin "A2") (pinfunction "OUT_A2") (pintype "power_in"))
    )
    (net (code "34") (name "Net-(C19-Pad2)") (class "Default")
      (node (ref "C19") (pin "2") (pinfunction "2_2") (pintype "passive"))
      (node (ref "R21") (pin "2") (pinfunction "2_2") (pintype "passive"))
    )
    (net (code "35") (name "Net-(C20-Pad2)") (class "Default")
      (node (ref "C20") (pin "2") (pinfunction "2_2") (pintype "passive"))
      (node (ref "R19") (pin "2") (pinfunction "2_2") (pintype "passive"))
    )
    (net (code "36") (name "Net-(C21-Pad2)") (class "Default")
      (node (ref "C21") (pin "2") (pinfunction "2_2") (pintype "passive"))
      (node (ref "P59") (pin "4") (pinfunction "4_4") (pintype "passive"))
    )
    (net (code "37") (name "Net-(C22-Pad1)") (class "Default")
      (node (ref "C22") (pin "1") (pinfunction "1_1") (pintype "passive"))
      (node (ref "P59") (pin "3") (pinfunction "3_3") (pintype "passive"))
    )
    (net (code "38") (name "Net-(P58-SLEEVE)") (class "Default")
      (node (ref "C19") (pin "1") (pinfunction "1_1") (pintype "passive"))
      (node (ref "P58") (pin "1") (pinfunction "SLEEVE_1") (pintype "passive"))
      (node (ref "R18") (pin "1") (pinfunction "1_1") (pintype "passive"))
    )
    (net (code "39") (name "Net-(P59-Pad1)") (class "Default")
      (node (ref "P59") (pin "1") (pinfunction "1_1") (pintype "passive"))
      (node (ref "R22") (pin "1") (pinfunction "1_1") (pintype "passive"))
    )
    (net (code "40") (name "Net-(P59-Pad2)") (class "Default")
      (node (ref "P59") (pin "2") (pinfunction "2_2") (pintype "passive"))
      (node (ref "R20") (pin "1") (pinfunction "1_1") (pintype "passive"))
    )
    (net (code "41") (name "Net-(P63-Pad8)") (class "Default")
      (node (ref "P63") (pin "8") (pinfunction "8_8") (pintype "passive"))
      (node (ref "R28") (pin "1") (pinfunction "1_1") (pintype "passive"))
    )
    (net (code "42") (name "Net-(P64-VPP)") (class "Default")
      (node (ref "P64") (pin "C6") (pinfunction "VPP_C6") (pintype "power_in"))
      (node (ref "R29") (pin "2") (pinfunction "2_2") (pintype "passive"))
    )
    (net (code "43") (name "Net-(U14A-VIN+)") (class "Default")
      (node (ref "R21") (pin "1") (pinfunction "1_1") (pintype "passive"))
      (node (ref "R24") (pin "2") (pinfunction "2_2") (pintype "passive"))
      (node (ref "U14") (pin "4") (pinfunction "VIN+_4") (pintype "input"))
    )
    (net (code "44") (name "Net-(U14A-VIN-)") (class "Default")
      (node (ref "R17") (pin "2") (pinfunction "2_2") (pintype "passive"))
      (node (ref "R19") (pin "1") (pinfunction "1_1") (pintype "passive"))
      (node (ref "U14") (pin "6") (pinfunction "VIN-_6") (pintype "input"))
    )
    (net (code "45") (name "Net-(U14A-VOUT+)") (class "Default")
      (node (ref "R17") (pin "1") (pinfunction "1_1") (pintype "passive"))
      (node (ref "R20") (pin "2") (pinfunction "2_2") (pintype "passive"))
      (node (ref "U14") (pin "9") (pinfunction "VOUT+_9") (pintype "output"))
    )
    (net (code "46") (name "Net-(U14A-VOUT-)") (class "Default")
      (node (ref "R22") (pin "2") (pinfunction "2_2") (pintype "passive"))
      (node (ref "R24") (pin "1") (pinfunction "1_1") (pintype "passive"))
      (node (ref "U14") (pin "1") (pinfunction "VOUT-_1") (pintype "output"))
    )
    (net (code "47") (name "Net-(U15-IN+)") (class "Default")
      (node (ref "C22") (pin "2") (pinfunction "2_2") (pintype "passive"))
      (node (ref "U15") (pin "A1") (pinfunction "IN+_A1") (pintype "input"))
    )
    (net (code "48") (name "Net-(U15-IN-)") (class "Default")
      (node (ref "C21") (pin "1") (pinfunction "1_1") (pintype "passive"))
      (node (ref "U15") (pin "C1") (pinfunction "IN-_C1") (pintype "input"))
    )
    (net (code "49") (name "Net-(U15-VO+)") (class "Default")
      (node (ref "TP11") (pin "1") (pinfunction "1_1") (pintype "passive"))
      (node (ref "U15") (pin "C3") (pinfunction "VO+_C3") (pintype "output"))
    )
    (net (code "50") (name "Net-(U15-VO-)") (class "Default")
      (node (ref "TP10") (pin "1") (pinfunction "1_1") (pintype "passive"))
      (node (ref "U15") (pin "A3") (pinfunction "VO-_A3") (pintype "output"))
    )
    (net (code "51") (name "P1.8V") (class "Default")
      (node (ref "P62") (pin "1") (pinfunction "1_1") (pintype "passive"))
      (node (ref "R23") (pin "2") (pinfunction "2_2") (pintype "passive"))
    )
    (net (code "52") (name "P3.3V") (class "Default")
      (node (ref "C15") (pin "1") (pinfunction "1_1") (pintype "passive"))
      (node (ref "C17") (pin "1") (pinfunction "1_1") (pintype "passive"))
      (node (ref "C18") (pin "1") (pinfunction "1_1") (pintype "passive"))
      (node (ref "C28") (pin "2") (pinfunction "2_2") (pintype "passive"))
      (node (ref "P61") (pin "18") (pinfunction "18_18") (pintype "passive"))
      (node (ref "P61") (pin "2") (pinfunction "2_2") (pintype "passive"))
      (node (ref "P62") (pin "3") (pinfunction "3_3") (pintype "passive"))
      (node (ref "U13") (pin "A1") (pinfunction "IN_A1") (pintype "input"))
      (node (ref "U13") (pin "B1") (pinfunction "EN_B1") (pintype "input"))
      (node (ref "U14") (pin "10") (pinfunction "VS+_10") (pintype "power_in"))
      (node (ref "U14") (pin "3") (pinfunction "~{PD}_3") (pintype "input"))
      (node (ref "U15") (pin "B1") (pinfunction "VDD_B1") (pintype "power_in"))
      (node (ref "U15") (pin "B2") (pinfunction "PVDD_B2") (pintype "power_in"))
      (node (ref "U15") (pin "C2") (pinfunction "EN_C2") (pintype "input"))
    )
    (net (code "53") (name "P5.0V") (class "Default")
      (node (ref "C25") (pin "1") (pinfunction "1_1") (pintype "passive"))
      (node (ref "C26") (pin "1") (pinfunction "1_1") (pintype "passive"))
      (node (ref "P61") (pin "1") (pinfunction "1_1") (pintype "passive"))
      (node (ref "P61") (pin "3") (pinfunction "3_3") (pintype "passive"))
      (node (ref "P63") (pin "6") (pinfunction "6_6") (pintype "passive"))
      (node (ref "P63") (pin "7") (pinfunction "7_7") (pintype "passive"))
      (node (ref "R28") (pin "2") (pinfunction "2_2") (pintype "passive"))
    )
    (net (code "54") (name "unconnected-(P12-Pad2)") (class "Default")
      (node (ref "P12") (pin "2") (pinfunction "2_2") (pintype "passive"))
    )
    (net (code "55") (name "unconnected-(P58-RING1-Pad3)") (class "Default")
      (node (ref "P58") (pin "3") (pinfunction "RING1_3") (pintype "passive"))
    )
    (net (code "56") (name "unconnected-(P58-RING1_SW-Pad6)") (class "Default")
      (node (ref "P58") (pin "6") (pinfunction "RING1_SW_6") (pintype "passive"))
    )
    (net (code "57") (name "unconnected-(P58-TIP_SW-Pad5)") (class "Default")
      (node (ref "P58") (pin "5") (pinfunction "TIP_SW_5") (pintype "passive"))
    )
    (net (code "58") (name "unconnected-(P60-Pad1)") (class "Default")
      (node (ref "P60") (pin "1") (pinfunction "1_1") (pintype "passive"))
    )
    (net (code "59") (name "unconnected-(P60-Pad2)") (class "Default")
      (node (ref "P60") (pin "2") (pinfunction "2_2") (pintype "passive"))
    )
    (net (code "60") (name "unconnected-(P60-Pad5)") (class "Default")
      (node (ref "P60") (pin "5") (pinfunction "5_5") (pintype "passive"))
    )
    (net (code "61") (name "unconnected-(P60-Pad7)") (class "Default")
      (node (ref "P60") (pin "7") (pinfunction "7_7") (pintype "passive"))
    )
    (net (code "62") (name "unconnected-(P60-Pad8)") (class "Default")
      (node (ref "P60") (pin "8") (pinfunction "8_8") (pintype "passive"))
    )
    (net (code "63") (name "unconnected-(P60-Pad10)") (class "Default")
      (node (ref "P60") (pin "10") (pinfunction "10_10") (pintype "passive"))
    )
    (net (code "64") (name "unconnected-(P60-Pad11)") (class "Default")
      (node (ref "P60") (pin "11") (pinfunction "11_11") (pintype "passive"))
    )
    (net (code "65") (name "unconnected-(P60-Pad15)") (class "Default")
      (node (ref "P60") (pin "15") (pinfunction "15_15") (pintype "passive"))
    )
    (net (code "66") (name "unconnected-(P60-Pad17)") (class "Default")
      (node (ref "P60") (pin "17") (pinfunction "17_17") (pintype "passive"))
    )
    (net (code "67") (name "unconnected-(P60-Pad19)") (class "Default")
      (node (ref "P60") (pin "19") (pinfunction "19_19") (pintype "passive"))
    )
    (net (code "68") (name "unconnected-(P61-Pad4)") (class "Default")
      (node (ref "P61") (pin "4") (pinfunction "4_4") (pintype "passive"))
    )
    (net (code "69") (name "unconnected-(P61-Pad6)") (class "Default")
      (node (ref "P61") (pin "6") (pinfunction "6_6") (pintype "passive"))
    )
    (net (code "70") (name "unconnected-(P61-Pad7)") (class "Default")
      (node (ref "P61") (pin "7") (pinfunction "7_7") (pintype "passive"))
    )
    (net (code "71") (name "unconnected-(P61-Pad8)") (class "Default")
      (node (ref "P61") (pin "8") (pinfunction "8_8") (pintype "passive"))
    )
    (net (code "72") (name "unconnected-(P61-Pad9)") (class "Default")
      (node (ref "P61") (pin "9") (pinfunction "9_9") (pintype "passive"))
    )
    (net (code "73") (name "unconnected-(P61-Pad11)") (class "Default")
      (node (ref "P61") (pin "11") (pinfunction "11_11") (pintype "passive"))
    )
    (net (code "74") (name "unconnected-(P61-Pad12)") (class "Default")
      (node (ref "P61") (pin "12") (pinfunction "12_12") (pintype "passive"))
    )
    (net (code "75") (name "unconnected-(P61-Pad14)") (class "Default")
      (node (ref "P61") (pin "14") (pinfunction "14_14") (pintype "passive"))
    )
    (net (code "76") (name "unconnected-(P61-Pad16)") (class "Default")
      (node (ref "P61") (pin "16") (pinfunction "16_16") (pintype "passive"))
    )
  )
)
